# 02-CPU_BOARD.net
KiCad netlist of a schematic drawn in Altium Designer
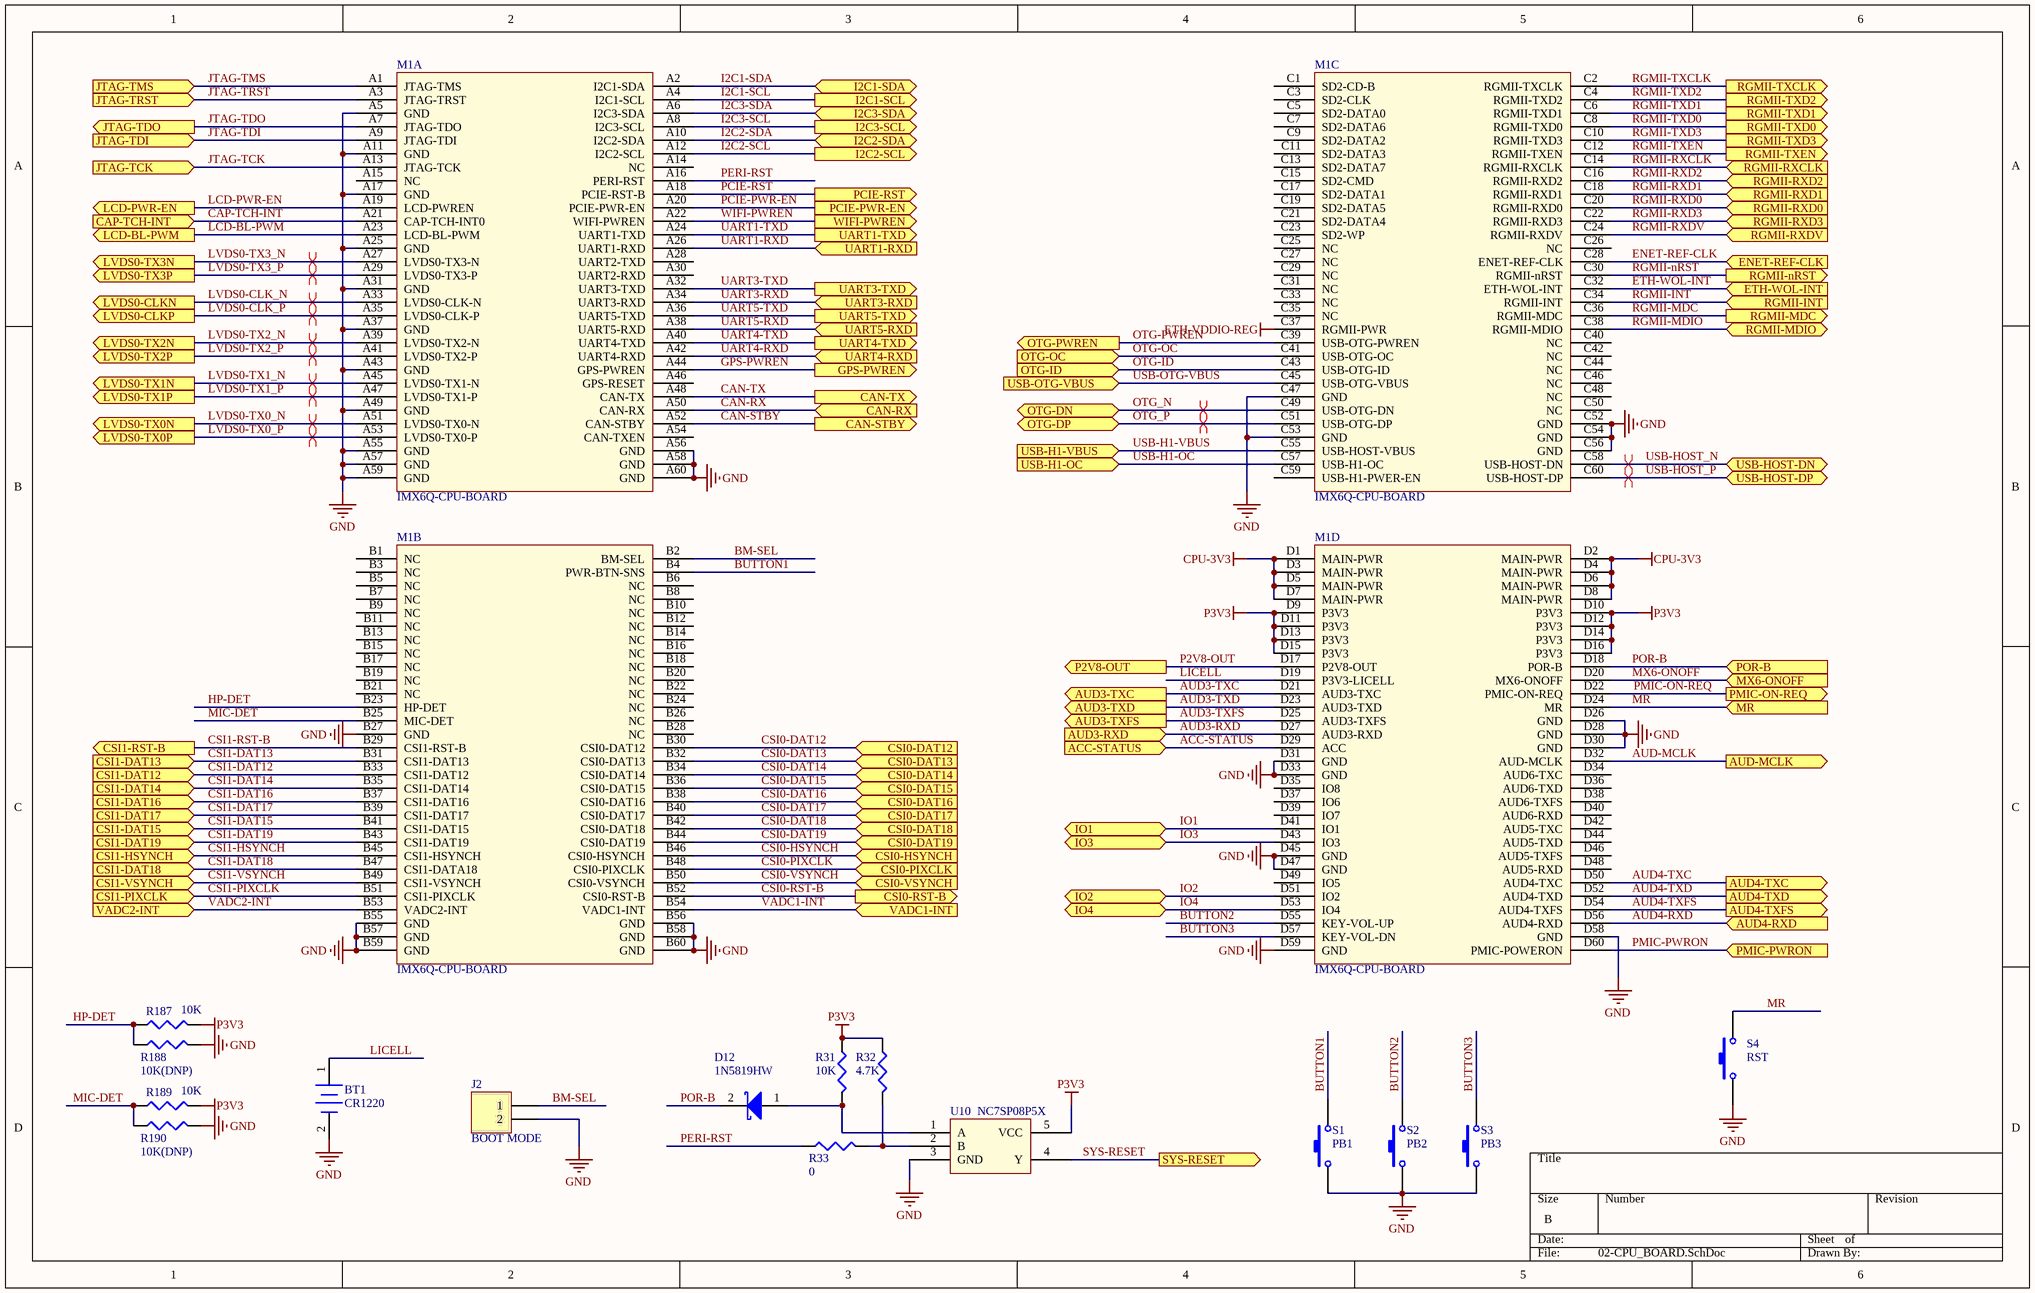
[diagram p0: 02-CPU_BOARD.SchDoc]

(export (version "E")
  (design (tool "Eeschema 10.0.6"))
  (components
    (comp (ref "BT1")
      (value "CR1220")
      (footprint "cr1220")
      (description "Multicell Battery")
      (fields (field (name "PUBLISHER") "Altium Limited"))
      (libsource (lib "Miscellaneous Devices") (part "Battery"))
    )
    (comp (ref "D12")
      (value "1N5819HW")
      (footprint "1N5819")
      (description "Schottky Rectifier")
      (libsource (lib "Miscellaneous Devices") (part "Diode 11DQ03"))
    )
    (comp (ref "J2")
      (value "BOOT MODE")
      (footprint "HDR1X2")
      (description "Header, 2-Pin")
      (fields (field (name "PUBLISHER") "Altium Limited"))
      (libsource (lib "Miscellaneous Connectors") (part "Header 2"))
    )
    (comp (ref "M1") (value "IMX6Q-CPU-BOARD") (libsource (lib "Schlib") (part "IMX6Q-CPU-BOARD")))
    (comp (ref "R31") (value "10K") (footprint "0402") (libsource (lib "*") (part "CR16-1003FM")))
    (comp (ref "R32") (value "4.7K") (footprint "0402") (libsource (lib "*") (part "CR16-1003FM")))
    (comp (ref "R33") (value "0") (footprint "0402") (libsource (lib "*") (part "CR16-1003FM")))
    (comp (ref "R187") (value "10K") (footprint "0402") (libsource (lib "*") (part "CR16-1003FM")))
    (comp (ref "R188") (value "10K(DNP)") (footprint "0402") (libsource (lib "*") (part "CR16-1003FM")))
    (comp (ref "R189") (value "10K") (footprint "0402") (libsource (lib "*") (part "CR16-1003FM")))
    (comp (ref "R190") (value "10K(DNP)") (footprint "0402") (libsource (lib "*") (part "CR16-1003FM")))
    (comp (ref "S1")
      (value "PB1")
      (footprint "SW-PB-SMD")
      (description "Switch")
      (fields (field (name "PUBLISHER") "Altium Limited"))
      (libsource (lib "Miscellaneous Devices") (part "SW-PB"))
    )
    (comp (ref "S2")
      (value "PB2")
      (footprint "SW-PB-SMD")
      (description "Switch")
      (fields (field (name "PUBLISHER") "Altium Limited"))
      (libsource (lib "Miscellaneous Devices") (part "SW-PB"))
    )
    (comp (ref "S3")
      (value "PB3")
      (footprint "SW-PB-SMD")
      (description "Switch")
      (fields (field (name "PUBLISHER") "Altium Limited"))
      (libsource (lib "Miscellaneous Devices") (part "SW-PB"))
    )
    (comp (ref "S4")
      (value "RST")
      (footprint "SW-PB-SMD")
      (description "Switch")
      (fields (field (name "PUBLISHER") "Altium Limited"))
      (libsource (lib "Miscellaneous Devices") (part "SW-PB"))
    )
    (comp (ref "U10") (value "NC7SP08P5X") (footprint "SC70") (libsource (lib "Schlib") (part "NC7SP08P5X")))
  )
  (nets
    (net (code "1") (name "/ACC-STATUS") (class "Default")
      (node (ref "M1") (pin "D29") (pinfunction "ACC_D29") (pintype "passive"))
    )
    (net (code "2") (name "/AUD-MCLK") (class "Default")
      (node (ref "M1") (pin "D32") (pinfunction "AUD-MCLK_D32") (pintype "passive"))
    )
    (net (code "3") (name "/AUD3-RXD") (class "Default")
      (node (ref "M1") (pin "D27") (pinfunction "AUD3-RXD_D27") (pintype "passive"))
    )
    (net (code "4") (name "/AUD3-TXC") (class "Default")
      (node (ref "M1") (pin "D21") (pinfunction "AUD3-TXC_D21") (pintype "passive"))
    )
    (net (code "5") (name "/AUD3-TXD") (class "Default")
      (node (ref "M1") (pin "D23") (pinfunction "AUD3-TXD_D23") (pintype "passive"))
    )
    (net (code "6") (name "/AUD3-TXFS") (class "Default")
      (node (ref "M1") (pin "D25") (pinfunction "AUD3-TXFS_D25") (pintype "passive"))
    )
    (net (code "7") (name "/AUD4-RXD") (class "Default")
      (node (ref "M1") (pin "D56") (pinfunction "AUD4-RXD_D56") (pintype "passive"))
    )
    (net (code "8") (name "/AUD4-TXC") (class "Default")
      (node (ref "M1") (pin "D50") (pinfunction "AUD4-TXC_D50") (pintype "passive"))
    )
    (net (code "9") (name "/AUD4-TXD") (class "Default")
      (node (ref "M1") (pin "D52") (pinfunction "AUD4-TXD_D52") (pintype "passive"))
    )
    (net (code "10") (name "/AUD4-TXFS") (class "Default")
      (node (ref "M1") (pin "D54") (pinfunction "AUD4-TXFS_D54") (pintype "passive"))
    )
    (net (code "11") (name "/BM-SEL") (class "Default")
      (node (ref "J2") (pin "1") (pinfunction "1_1") (pintype "passive"))
      (node (ref "M1") (pin "B2") (pinfunction "BM-SEL_B2") (pintype "passive"))
    )
    (net (code "12") (name "/BUTTON1") (class "Default")
      (node (ref "M1") (pin "B4") (pinfunction "PWR-BTN-SNS_B4") (pintype "passive"))
      (node (ref "S1") (pin "2") (pinfunction "2_2") (pintype "passive"))
    )
    (net (code "13") (name "/BUTTON2") (class "Default")
      (node (ref "M1") (pin "D55") (pinfunction "KEY-VOL-UP_D55") (pintype "passive"))
      (node (ref "S2") (pin "2") (pinfunction "2_2") (pintype "passive"))
    )
    (net (code "14") (name "/BUTTON3") (class "Default")
      (node (ref "M1") (pin "D57") (pinfunction "KEY-VOL-DN_D57") (pintype "passive"))
      (node (ref "S3") (pin "2") (pinfunction "2_2") (pintype "passive"))
    )
    (net (code "15") (name "/CAN-RX") (class "Default")
      (node (ref "M1") (pin "A50") (pinfunction "CAN-RX_A50") (pintype "passive"))
    )
    (net (code "16") (name "/CAN-STBY") (class "Default")
      (node (ref "M1") (pin "A52") (pinfunction "CAN-STBY_A52") (pintype "passive"))
    )
    (net (code "17") (name "/CAN-TX") (class "Default")
      (node (ref "M1") (pin "A48") (pinfunction "CAN-TX_A48") (pintype "passive"))
    )
    (net (code "18") (name "/CAP-TCH-INT") (class "Default")
      (node (ref "M1") (pin "A21") (pinfunction "CAP-TCH-INT0_A21") (pintype "passive"))
    )
    (net (code "19") (name "/CSI0-DAT12") (class "Default")
      (node (ref "M1") (pin "B30") (pinfunction "CSI0-DAT12_B30") (pintype "passive"))
    )
    (net (code "20") (name "/CSI0-DAT13") (class "Default")
      (node (ref "M1") (pin "B32") (pinfunction "CSI0-DAT13_B32") (pintype "passive"))
    )
    (net (code "21") (name "/CSI0-DAT14") (class "Default")
      (node (ref "M1") (pin "B34") (pinfunction "CSI0-DAT14_B34") (pintype "passive"))
    )
    (net (code "22") (name "/CSI0-DAT15") (class "Default")
      (node (ref "M1") (pin "B36") (pinfunction "CSI0-DAT15_B36") (pintype "passive"))
    )
    (net (code "23") (name "/CSI0-DAT16") (class "Default")
      (node (ref "M1") (pin "B38") (pinfunction "CSI0-DAT16_B38") (pintype "passive"))
    )
    (net (code "24") (name "/CSI0-DAT17") (class "Default")
      (node (ref "M1") (pin "B40") (pinfunction "CSI0-DAT17_B40") (pintype "passive"))
    )
    (net (code "25") (name "/CSI0-DAT18") (class "Default")
      (node (ref "M1") (pin "B42") (pinfunction "CSI0-DAT18_B42") (pintype "passive"))
    )
    (net (code "26") (name "/CSI0-DAT19") (class "Default")
      (node (ref "M1") (pin "B44") (pinfunction "CSI0-DAT19_B44") (pintype "passive"))
    )
    (net (code "27") (name "/CSI0-HSYNCH") (class "Default")
      (node (ref "M1") (pin "B46") (pinfunction "CSI0-HSYNCH_B46") (pintype "passive"))
    )
    (net (code "28") (name "/CSI0-PIXCLK") (class "Default")
      (node (ref "M1") (pin "B48") (pinfunction "CSI0-PIXCLK_B48") (pintype "passive"))
    )
    (net (code "29") (name "/CSI0-RST-B") (class "Default")
      (node (ref "M1") (pin "B52") (pinfunction "CSI0-RST-B_B52") (pintype "passive"))
    )
    (net (code "30") (name "/CSI0-VSYNCH") (class "Default")
      (node (ref "M1") (pin "B50") (pinfunction "CSI0-VSYNCH_B50") (pintype "passive"))
    )
    (net (code "31") (name "/CSI1-DAT12") (class "Default")
      (node (ref "M1") (pin "B33") (pinfunction "CSI1-DAT12_B33") (pintype "passive"))
    )
    (net (code "32") (name "/CSI1-DAT13") (class "Default")
      (node (ref "M1") (pin "B31") (pinfunction "CSI1-DAT13_B31") (pintype "passive"))
    )
    (net (code "33") (name "/CSI1-DAT14") (class "Default")
      (node (ref "M1") (pin "B35") (pinfunction "CSI1-DAT14_B35") (pintype "passive"))
    )
    (net (code "34") (name "/CSI1-DAT15") (class "Default")
      (node (ref "M1") (pin "B41") (pinfunction "CSI1-DAT15_B41") (pintype "passive"))
    )
    (net (code "35") (name "/CSI1-DAT16") (class "Default")
      (node (ref "M1") (pin "B37") (pinfunction "CSI1-DAT16_B37") (pintype "passive"))
    )
    (net (code "36") (name "/CSI1-DAT17") (class "Default")
      (node (ref "M1") (pin "B39") (pinfunction "CSI1-DAT17_B39") (pintype "passive"))
    )
    (net (code "37") (name "/CSI1-DAT18") (class "Default")
      (node (ref "M1") (pin "B47") (pinfunction "CSI1-DATA18_B47") (pintype "passive"))
    )
    (net (code "38") (name "/CSI1-DAT19") (class "Default")
      (node (ref "M1") (pin "B43") (pinfunction "CSI1-DAT19_B43") (pintype "passive"))
    )
    (net (code "39") (name "/CSI1-HSYNCH") (class "Default")
      (node (ref "M1") (pin "B45") (pinfunction "CSI1-HSYNCH_B45") (pintype "passive"))
    )
    (net (code "40") (name "/CSI1-PIXCLK") (class "Default")
      (node (ref "M1") (pin "B51") (pinfunction "CSI1-PIXCLK_B51") (pintype "passive"))
    )
    (net (code "41") (name "/CSI1-RST-B") (class "Default")
      (node (ref "M1") (pin "B29") (pinfunction "CSI1-RST-B_B29") (pintype "passive"))
    )
    (net (code "42") (name "/CSI1-VSYNCH") (class "Default")
      (node (ref "M1") (pin "B49") (pinfunction "CSI1-VSYNCH_B49") (pintype "passive"))
    )
    (net (code "43") (name "/ENET-REF-CLK") (class "Default")
      (node (ref "M1") (pin "C28") (pinfunction "ENET-REF-CLK_C28") (pintype "passive"))
    )
    (net (code "44") (name "/ETH-WOL-INT") (class "Default")
      (node (ref "M1") (pin "C32") (pinfunction "ETH-WOL-INT_C32") (pintype "passive"))
    )
    (net (code "45") (name "/GPS-PWREN") (class "Default")
      (node (ref "M1") (pin "A44") (pinfunction "GPS-PWREN_A44") (pintype "passive"))
    )
    (net (code "46") (name "/HP-DET") (class "Default")
      (node (ref "M1") (pin "B23") (pinfunction "HP-DET_B23") (pintype "passive"))
      (node (ref "R187") (pin "1") (pinfunction "1_1") (pintype "passive"))
      (node (ref "R188") (pin "1") (pinfunction "1_1") (pintype "passive"))
    )
    (net (code "47") (name "/I2C1-SCL") (class "Default")
      (node (ref "M1") (pin "A4") (pinfunction "I2C1-SCL_A4") (pintype "passive"))
    )
    (net (code "48") (name "/I2C1-SDA") (class "Default")
      (node (ref "M1") (pin "A2") (pinfunction "I2C1-SDA_A2") (pintype "passive"))
    )
    (net (code "49") (name "/I2C2-SCL") (class "Default")
      (node (ref "M1") (pin "A12") (pinfunction "I2C2-SCL_A12") (pintype "passive"))
    )
    (net (code "50") (name "/I2C2-SDA") (class "Default")
      (node (ref "M1") (pin "A10") (pinfunction "I2C2-SDA_A10") (pintype "passive"))
    )
    (net (code "51") (name "/I2C3-SCL") (class "Default")
      (node (ref "M1") (pin "A8") (pinfunction "I2C3-SCL_A8") (pintype "passive"))
    )
    (net (code "52") (name "/I2C3-SDA") (class "Default")
      (node (ref "M1") (pin "A6") (pinfunction "I2C3-SDA_A6") (pintype "passive"))
    )
    (net (code "53") (name "/IO1") (class "Default")
      (node (ref "M1") (pin "D41") (pinfunction "IO1_D41") (pintype "passive"))
    )
    (net (code "54") (name "/IO2") (class "Default")
      (node (ref "M1") (pin "D51") (pinfunction "IO2_D51") (pintype "passive"))
    )
    (net (code "55") (name "/IO3") (class "Default")
      (node (ref "M1") (pin "D43") (pinfunction "IO3_D43") (pintype "passive"))
    )
    (net (code "56") (name "/IO4") (class "Default")
      (node (ref "M1") (pin "D53") (pinfunction "IO4_D53") (pintype "passive"))
    )
    (net (code "57") (name "/JTAG-TCK") (class "Default")
      (node (ref "M1") (pin "A13") (pinfunction "JTAG-TCK_A13") (pintype "passive"))
    )
    (net (code "58") (name "/JTAG-TDI") (class "Default")
      (node (ref "M1") (pin "A9") (pinfunction "JTAG-TDI_A9") (pintype "passive"))
    )
    (net (code "59") (name "/JTAG-TDO") (class "Default")
      (node (ref "M1") (pin "A7") (pinfunction "JTAG-TDO_A7") (pintype "passive"))
    )
    (net (code "60") (name "/JTAG-TMS") (class "Default")
      (node (ref "M1") (pin "A1") (pinfunction "JTAG-TMS_A1") (pintype "passive"))
    )
    (net (code "61") (name "/JTAG-TRST") (class "Default")
      (node (ref "M1") (pin "A3") (pinfunction "JTAG-TRST_A3") (pintype "passive"))
    )
    (net (code "62") (name "/LCD-BL-PWM") (class "Default")
      (node (ref "M1") (pin "A23") (pinfunction "LCD-BL-PWM_A23") (pintype "passive"))
    )
    (net (code "63") (name "/LCD-PWR-EN") (class "Default")
      (node (ref "M1") (pin "A19") (pinfunction "LCD-PWREN_A19") (pintype "passive"))
    )
    (net (code "64") (name "/LICELL") (class "Default")
      (node (ref "BT1") (pin "1") (pinfunction "+_1") (pintype "passive"))
      (node (ref "M1") (pin "D19") (pinfunction "P3V3-LICELL_D19") (pintype "passive"))
    )
    (net (code "65") (name "/LVDS0-CLK_N") (class "Default")
      (node (ref "M1") (pin "A33") (pinfunction "LVDS0-CLK-N_A33") (pintype "passive"))
    )
    (net (code "66") (name "/LVDS0-CLK_P") (class "Default")
      (node (ref "M1") (pin "A35") (pinfunction "LVDS0-CLK-P_A35") (pintype "passive"))
    )
    (net (code "67") (name "/LVDS0-TX0_N") (class "Default")
      (node (ref "M1") (pin "A51") (pinfunction "LVDS0-TX0-N_A51") (pintype "passive"))
    )
    (net (code "68") (name "/LVDS0-TX0_P") (class "Default")
      (node (ref "M1") (pin "A53") (pinfunction "LVDS0-TX0-P_A53") (pintype "passive"))
    )
    (net (code "69") (name "/LVDS0-TX1_N") (class "Default")
      (node (ref "M1") (pin "A45") (pinfunction "LVDS0-TX1-N_A45") (pintype "passive"))
    )
    (net (code "70") (name "/LVDS0-TX1_P") (class "Default")
      (node (ref "M1") (pin "A47") (pinfunction "LVDS0-TX1-P_A47") (pintype "passive"))
    )
    (net (code "71") (name "/LVDS0-TX2_N") (class "Default")
      (node (ref "M1") (pin "A39") (pinfunction "LVDS0-TX2-N_A39") (pintype "passive"))
    )
    (net (code "72") (name "/LVDS0-TX2_P") (class "Default")
      (node (ref "M1") (pin "A41") (pinfunction "LVDS0-TX2-P_A41") (pintype "passive"))
    )
    (net (code "73") (name "/LVDS0-TX3_N") (class "Default")
      (node (ref "M1") (pin "A27") (pinfunction "LVDS0-TX3-N_A27") (pintype "passive"))
    )
    (net (code "74") (name "/LVDS0-TX3_P") (class "Default")
      (node (ref "M1") (pin "A29") (pinfunction "LVDS0-TX3-P_A29") (pintype "passive"))
    )
    (net (code "75") (name "/MIC-DET") (class "Default")
      (node (ref "M1") (pin "B25") (pinfunction "MIC-DET_B25") (pintype "passive"))
      (node (ref "R189") (pin "1") (pinfunction "1_1") (pintype "passive"))
      (node (ref "R190") (pin "1") (pinfunction "1_1") (pintype "passive"))
    )
    (net (code "76") (name "/MR") (class "Default")
      (node (ref "M1") (pin "D24") (pinfunction "MR_D24") (pintype "passive"))
      (node (ref "S4") (pin "2") (pinfunction "2_2") (pintype "passive"))
    )
    (net (code "77") (name "/MX6-ONOFF") (class "Default")
      (node (ref "M1") (pin "D20") (pinfunction "MX6-ONOFF_D20") (pintype "passive"))
    )
    (net (code "78") (name "/OTG-ID") (class "Default")
      (node (ref "M1") (pin "C43") (pinfunction "USB-OTG-ID_C43") (pintype "passive"))
    )
    (net (code "79") (name "/OTG-OC") (class "Default")
      (node (ref "M1") (pin "C41") (pinfunction "USB-OTG-OC_C41") (pintype "passive"))
    )
    (net (code "80") (name "/OTG-PWREN") (class "Default")
      (node (ref "M1") (pin "C39") (pinfunction "USB-OTG-PWREN_C39") (pintype "passive"))
    )
    (net (code "81") (name "/OTG_N") (class "Default")
      (node (ref "M1") (pin "C49") (pinfunction "USB-OTG-DN_C49") (pintype "passive"))
    )
    (net (code "82") (name "/OTG_P") (class "Default")
      (node (ref "M1") (pin "C51") (pinfunction "USB-OTG-DP_C51") (pintype "passive"))
    )
    (net (code "83") (name "/P2V8-OUT") (class "Default")
      (node (ref "M1") (pin "D17") (pinfunction "P2V8-OUT_D17") (pintype "passive"))
    )
    (net (code "84") (name "/PCIE-PWR-EN") (class "Default")
      (node (ref "M1") (pin "A20") (pinfunction "PCIE-PWR-EN_A20") (pintype "passive"))
    )
    (net (code "85") (name "/PCIE-RST") (class "Default")
      (node (ref "M1") (pin "A18") (pinfunction "PCIE-RST-B_A18") (pintype "passive"))
    )
    (net (code "86") (name "/PERI-RST") (class "Default")
      (node (ref "M1") (pin "A16") (pinfunction "PERI-RST_A16") (pintype "passive"))
      (node (ref "R33") (pin "1") (pinfunction "1_1") (pintype "passive"))
    )
    (net (code "87") (name "/PMIC-ON-REQ") (class "Default")
      (node (ref "M1") (pin "D22") (pinfunction "PMIC-ON-REQ_D22") (pintype "passive"))
    )
    (net (code "88") (name "/PMIC-PWRON") (class "Default")
      (node (ref "M1") (pin "D60") (pinfunction "PMIC-POWERON_D60") (pintype "passive"))
    )
    (net (code "89") (name "/POR-B") (class "Default")
      (node (ref "D12") (pin "2") (pinfunction "K_2") (pintype "passive"))
      (node (ref "M1") (pin "D18") (pinfunction "POR-B_D18") (pintype "passive"))
    )
    (net (code "90") (name "/RGMII-INT") (class "Default")
      (node (ref "M1") (pin "C34") (pinfunction "RGMII-INT_C34") (pintype "passive"))
    )
    (net (code "91") (name "/RGMII-MDC") (class "Default")
      (node (ref "M1") (pin "C36") (pinfunction "RGMII-MDC_C36") (pintype "passive"))
    )
    (net (code "92") (name "/RGMII-MDIO") (class "Default")
      (node (ref "M1") (pin "C38") (pinfunction "RGMII-MDIO_C38") (pintype "passive"))
    )
    (net (code "93") (name "/RGMII-RXCLK") (class "Default")
      (node (ref "M1") (pin "C14") (pinfunction "RGMII-RXCLK_C14") (pintype "passive"))
    )
    (net (code "94") (name "/RGMII-RXD0") (class "Default")
      (node (ref "M1") (pin "C20") (pinfunction "RGMII-RXD0_C20") (pintype "passive"))
    )
    (net (code "95") (name "/RGMII-RXD1") (class "Default")
      (node (ref "M1") (pin "C18") (pinfunction "RGMII-RXD1_C18") (pintype "passive"))
    )
    (net (code "96") (name "/RGMII-RXD2") (class "Default")
      (node (ref "M1") (pin "C16") (pinfunction "RGMII-RXD2_C16") (pintype "passive"))
    )
    (net (code "97") (name "/RGMII-RXD3") (class "Default")
      (node (ref "M1") (pin "C22") (pinfunction "RGMII-RXD3_C22") (pintype "passive"))
    )
    (net (code "98") (name "/RGMII-RXDV") (class "Default")
      (node (ref "M1") (pin "C24") (pinfunction "RGMII-RXDV_C24") (pintype "passive"))
    )
    (net (code "99") (name "/RGMII-TXCLK") (class "Default")
      (node (ref "M1") (pin "C2") (pinfunction "RGMII-TXCLK_C2") (pintype "passive"))
    )
    (net (code "100") (name "/RGMII-TXD0") (class "Default")
      (node (ref "M1") (pin "C8") (pinfunction "RGMII-TXD0_C8") (pintype "passive"))
    )
    (net (code "101") (name "/RGMII-TXD1") (class "Default")
      (node (ref "M1") (pin "C6") (pinfunction "RGMII-TXD1_C6") (pintype "passive"))
    )
    (net (code "102") (name "/RGMII-TXD2") (class "Default")
      (node (ref "M1") (pin "C4") (pinfunction "RGMII-TXD2_C4") (pintype "passive"))
    )
    (net (code "103") (name "/RGMII-TXD3") (class "Default")
      (node (ref "M1") (pin "C10") (pinfunction "RGMII-TXD3_C10") (pintype "passive"))
    )
    (net (code "104") (name "/RGMII-TXEN") (class "Default")
      (node (ref "M1") (pin "C12") (pinfunction "RGMII-TXEN_C12") (pintype "passive"))
    )
    (net (code "105") (name "/RGMII-nRST") (class "Default")
      (node (ref "M1") (pin "C30") (pinfunction "RGMII-nRST_C30") (pintype "passive"))
    )
    (net (code "106") (name "/SYS-RESET") (class "Default")
      (node (ref "U10") (pin "4") (pinfunction "Y_4") (pintype "passive"))
    )
    (net (code "107") (name "/UART1-RXD") (class "Default")
      (node (ref "M1") (pin "A26") (pinfunction "UART1-RXD_A26") (pintype "passive"))
    )
    (net (code "108") (name "/UART1-TXD") (class "Default")
      (node (ref "M1") (pin "A24") (pinfunction "UART1-TXD_A24") (pintype "passive"))
    )
    (net (code "109") (name "/UART3-RXD") (class "Default")
      (node (ref "M1") (pin "A34") (pinfunction "UART3-RXD_A34") (pintype "passive"))
    )
    (net (code "110") (name "/UART3-TXD") (class "Default")
      (node (ref "M1") (pin "A32") (pinfunction "UART3-TXD_A32") (pintype "passive"))
    )
    (net (code "111") (name "/UART4-RXD") (class "Default")
      (node (ref "M1") (pin "A42") (pinfunction "UART4-RXD_A42") (pintype "passive"))
    )
    (net (code "112") (name "/UART4-TXD") (class "Default")
      (node (ref "M1") (pin "A40") (pinfunction "UART4-TXD_A40") (pintype "passive"))
    )
    (net (code "113") (name "/UART5-RXD") (class "Default")
      (node (ref "M1") (pin "A38") (pinfunction "UART5-RXD_A38") (pintype "passive"))
    )
    (net (code "114") (name "/UART5-TXD") (class "Default")
      (node (ref "M1") (pin "A36") (pinfunction "UART5-TXD_A36") (pintype "passive"))
    )
    (net (code "115") (name "/USB-H1-OC") (class "Default")
      (node (ref "M1") (pin "C57") (pinfunction "USB-H1-OC_C57") (pintype "passive"))
    )
    (net (code "116") (name "/USB-H1-VBUS") (class "Default")
      (node (ref "M1") (pin "C55") (pinfunction "USB-HOST-VBUS_C55") (pintype "passive"))
    )
    (net (code "117") (name "/USB-HOST_N") (class "Default")
      (node (ref "M1") (pin "C58") (pinfunction "USB-HOST-DN_C58") (pintype "passive"))
    )
    (net (code "118") (name "/USB-HOST_P") (class "Default")
      (node (ref "M1") (pin "C60") (pinfunction "USB-HOST-DP_C60") (pintype "passive"))
    )
    (net (code "119") (name "/USB-OTG-VBUS") (class "Default")
      (node (ref "M1") (pin "C45") (pinfunction "USB-OTG-VBUS_C45") (pintype "passive"))
    )
    (net (code "120") (name "/VADC1-INT") (class "Default")
      (node (ref "M1") (pin "B54") (pinfunction "VADC1-INT_B54") (pintype "passive"))
    )
    (net (code "121") (name "/VADC2-INT") (class "Default")
      (node (ref "M1") (pin "B53") (pinfunction "VADC2-INT_B53") (pintype "passive"))
    )
    (net (code "122") (name "/WIFI-PWREN") (class "Default")
      (node (ref "M1") (pin "A22") (pinfunction "WIFI-PWREN_A22") (pintype "passive"))
    )
    (net (code "123") (name "CPU-3V3") (class "Default")
      (node (ref "M1") (pin "D1") (pinfunction "MAIN-PWR_D1") (pintype "passive"))
      (node (ref "M1") (pin "D2") (pinfunction "MAIN-PWR_D2") (pintype "passive"))
      (node (ref "M1") (pin "D3") (pinfunction "MAIN-PWR_D3") (pintype "passive"))
      (node (ref "M1") (pin "D4") (pinfunction "MAIN-PWR_D4") (pintype "passive"))
      (node (ref "M1") (pin "D5") (pinfunction "MAIN-PWR_D5") (pintype "passive"))
      (node (ref "M1") (pin "D6") (pinfunction "MAIN-PWR_D6") (pintype "passive"))
      (node (ref "M1") (pin "D7") (pinfunction "MAIN-PWR_D7") (pintype "passive"))
      (node (ref "M1") (pin "D8") (pinfunction "MAIN-PWR_D8") (pintype "passive"))
    )
    (net (code "124") (name "ETH-VDDIO-REG") (class "Default")
      (node (ref "M1") (pin "C37") (pinfunction "RGMII-PWR_C37") (pintype "passive"))
    )
    (net (code "125") (name "GND") (class "Default")
      (node (ref "BT1") (pin "2") (pinfunction "-_2") (pintype "passive"))
      (node (ref "J2") (pin "2") (pinfunction "2_2") (pintype "passive"))
      (node (ref "M1") (pin "A11") (pinfunction "GND_A11") (pintype "passive"))
      (node (ref "M1") (pin "A17") (pinfunction "GND_A17") (pintype "passive"))
      (node (ref "M1") (pin "A25") (pinfunction "GND_A25") (pintype "passive"))
      (node (ref "M1") (pin "A31") (pinfunction "GND_A31") (pintype "passive"))
      (node (ref "M1") (pin "A37") (pinfunction "GND_A37") (pintype "passive"))
      (node (ref "M1") (pin "A43") (pinfunction "GND_A43") (pintype "passive"))
      (node (ref "M1") (pin "A49") (pinfunction "GND_A49") (pintype "passive"))
      (node (ref "M1") (pin "A5") (pinfunction "GND_A5") (pintype "passive"))
      (node (ref "M1") (pin "A55") (pinfunction "GND_A55") (pintype "passive"))
      (node (ref "M1") (pin "A56") (pinfunction "GND_A56") (pintype "passive"))
      (node (ref "M1") (pin "A57") (pinfunction "GND_A57") (pintype "passive"))
      (node (ref "M1") (pin "A58") (pinfunction "GND_A58") (pintype "passive"))
      (node (ref "M1") (pin "A59") (pinfunction "GND_A59") (pintype "passive"))
      (node (ref "M1") (pin "A60") (pinfunction "GND_A60") (pintype "passive"))
      (node (ref "M1") (pin "B27") (pinfunction "GND_B27") (pintype "passive"))
      (node (ref "M1") (pin "B55") (pinfunction "GND_B55") (pintype "passive"))
      (node (ref "M1") (pin "B56") (pinfunction "GND_B56") (pintype "passive"))
      (node (ref "M1") (pin "B57") (pinfunction "GND_B57") (pintype "passive"))
      (node (ref "M1") (pin "B58") (pinfunction "GND_B58") (pintype "passive"))
      (node (ref "M1") (pin "B59") (pinfunction "GND_B59") (pintype "passive"))
      (node (ref "M1") (pin "B60") (pinfunction "GND_B60") (pintype "passive"))
      (node (ref "M1") (pin "C47") (pinfunction "GND_C47") (pintype "passive"))
      (node (ref "M1") (pin "C52") (pinfunction "GND_C52") (pintype "passive"))
      (node (ref "M1") (pin "C53") (pinfunction "GND_C53") (pintype "passive"))
      (node (ref "M1") (pin "C54") (pinfunction "GND_C54") (pintype "passive"))
      (node (ref "M1") (pin "C56") (pinfunction "GND_C56") (pintype "passive"))
      (node (ref "M1") (pin "D26") (pinfunction "GND_D26") (pintype "passive"))
      (node (ref "M1") (pin "D28") (pinfunction "GND_D28") (pintype "passive"))
      (node (ref "M1") (pin "D30") (pinfunction "GND_D30") (pintype "passive"))
      (node (ref "M1") (pin "D31") (pinfunction "GND_D31") (pintype "passive"))
      (node (ref "M1") (pin "D33") (pinfunction "GND_D33") (pintype "passive"))
      (node (ref "M1") (pin "D45") (pinfunction "GND_D45") (pintype "passive"))
      (node (ref "M1") (pin "D47") (pinfunction "GND_D47") (pintype "passive"))
      (node (ref "M1") (pin "D58") (pinfunction "GND_D58") (pintype "passive"))
      (node (ref "M1") (pin "D59") (pinfunction "GND_D59") (pintype "passive"))
      (node (ref "R188") (pin "2") (pinfunction "2_2") (pintype "passive"))
      (node (ref "R190") (pin "2") (pinfunction "2_2") (pintype "passive"))
      (node (ref "S1") (pin "1") (pinfunction "1_1") (pintype "passive"))
      (node (ref "S2") (pin "1") (pinfunction "1_1") (pintype "passive"))
      (node (ref "S3") (pin "1") (pinfunction "1_1") (pintype "passive"))
      (node (ref "S4") (pin "1") (pinfunction "1_1") (pintype "passive"))
      (node (ref "U10") (pin "3") (pinfunction "GND_3") (pintype "passive"))
    )
    (net (code "126") (name "Net-(D12-A)") (class "Default")
      (node (ref "D12") (pin "1") (pinfunction "A_1") (pintype "passive"))
      (node (ref "R31") (pin "2") (pinfunction "2_2") (pintype "passive"))
      (node (ref "U10") (pin "1") (pinfunction "A_1") (pintype "passive"))
    )
    (net (code "127") (name "Net-(U10-B)") (class "Default")
      (node (ref "R32") (pin "2") (pinfunction "2_2") (pintype "passive"))
      (node (ref "R33") (pin "2") (pinfunction "2_2") (pintype "passive"))
      (node (ref "U10") (pin "2") (pinfunction "B_2") (pintype "passive"))
    )
    (net (code "128") (name "P3V3") (class "Default")
      (node (ref "M1") (pin "D10") (pinfunction "P3V3_D10") (pintype "passive"))
      (node (ref "M1") (pin "D11") (pinfunction "P3V3_D11") (pintype "passive"))
      (node (ref "M1") (pin "D12") (pinfunction "P3V3_D12") (pintype "passive"))
      (node (ref "M1") (pin "D13") (pinfunction "P3V3_D13") (pintype "passive"))
      (node (ref "M1") (pin "D14") (pinfunction "P3V3_D14") (pintype "passive"))
      (node (ref "M1") (pin "D15") (pinfunction "P3V3_D15") (pintype "passive"))
      (node (ref "M1") (pin "D16") (pinfunction "P3V3_D16") (pintype "passive"))
      (node (ref "M1") (pin "D9") (pinfunction "P3V3_D9") (pintype "passive"))
      (node (ref "R187") (pin "2") (pinfunction "2_2") (pintype "passive"))
      (node (ref "R189") (pin "2") (pinfunction "2_2") (pintype "passive"))
      (node (ref "R31") (pin "1") (pinfunction "1_1") (pintype "passive"))
      (node (ref "R32") (pin "1") (pinfunction "1_1") (pintype "passive"))
      (node (ref "U10") (pin "5") (pinfunction "VCC_5") (pintype "passive"))
    )
    (net (code "129") (name "unconnected-(M1A-CAN-TXEN-PadA54)") (class "Default")
      (node (ref "M1") (pin "A54") (pinfunction "CAN-TXEN_A54") (pintype "passive"))
    )
    (net (code "130") (name "unconnected-(M1A-GPS-RESET-PadA46)") (class "Default")
      (node (ref "M1") (pin "A46") (pinfunction "GPS-RESET_A46") (pintype "passive"))
    )
    (net (code "131") (name "unconnected-(M1A-NC-PadA14)") (class "Default")
      (node (ref "M1") (pin "A14") (pinfunction "NC_A14") (pintype "passive"))
    )
    (net (code "132") (name "unconnected-(M1A-NC-PadA15)") (class "Default")
      (node (ref "M1") (pin "A15") (pinfunction "NC_A15") (pintype "passive"))
    )
    (net (code "133") (name "unconnected-(M1A-UART2-RXD-PadA30)") (class "Default")
      (node (ref "M1") (pin "A30") (pinfunction "UART2-RXD_A30") (pintype "passive"))
    )
    (net (code "134") (name "unconnected-(M1A-UART2-TXD-PadA28)") (class "Default")
      (node (ref "M1") (pin "A28") (pinfunction "UART2-TXD_A28") (pintype "passive"))
    )
    (net (code "135") (name "unconnected-(M1B-NC-PadB1)") (class "Default")
      (node (ref "M1") (pin "B1") (pinfunction "NC_B1") (pintype "passive"))
    )
    (net (code "136") (name "unconnected-(M1B-NC-PadB3)") (class "Default")
      (node (ref "M1") (pin "B3") (pinfunction "NC_B3") (pintype "passive"))
    )
    (net (code "137") (name "unconnected-(M1B-NC-PadB5)") (class "Default")
      (node (ref "M1") (pin "B5") (pinfunction "NC_B5") (pintype "passive"))
    )
    (net (code "138") (name "unconnected-(M1B-NC-PadB6)") (class "Default")
      (node (ref "M1") (pin "B6") (pinfunction "NC_B6") (pintype "passive"))
    )
    (net (code "139") (name "unconnected-(M1B-NC-PadB7)") (class "Default")
      (node (ref "M1") (pin "B7") (pinfunction "NC_B7") (pintype "passive"))
    )
    (net (code "140") (name "unconnected-(M1B-NC-PadB8)") (class "Default")
      (node (ref "M1") (pin "B8") (pinfunction "NC_B8") (pintype "passive"))
    )
    (net (code "141") (name "unconnected-(M1B-NC-PadB9)") (class "Default")
      (node (ref "M1") (pin "B9") (pinfunction "NC_B9") (pintype "passive"))
    )
    (net (code "142") (name "unconnected-(M1B-NC-PadB10)") (class "Default")
      (node (ref "M1") (pin "B10") (pinfunction "NC_B10") (pintype "passive"))
    )
    (net (code "143") (name "unconnected-(M1B-NC-PadB11)") (class "Default")
      (node (ref "M1") (pin "B11") (pinfunction "NC_B11") (pintype "passive"))
    )
    (net (code "144") (name "unconnected-(M1B-NC-PadB12)") (class "Default")
      (node (ref "M1") (pin "B12") (pinfunction "NC_B12") (pintype "passive"))
    )
    (net (code "145") (name "unconnected-(M1B-NC-PadB13)") (class "Default")
      (node (ref "M1") (pin "B13") (pinfunction "NC_B13") (pintype "passive"))
    )
    (net (code "146") (name "unconnected-(M1B-NC-PadB14)") (class "Default")
      (node (ref "M1") (pin "B14") (pinfunction "NC_B14") (pintype "passive"))
    )
    (net (code "147") (name "unconnected-(M1B-NC-PadB15)") (class "Default")
      (node (ref "M1") (pin "B15") (pinfunction "NC_B15") (pintype "passive"))
    )
    (net (code "148") (name "unconnected-(M1B-NC-PadB16)") (class "Default")
      (node (ref "M1") (pin "B16") (pinfunction "NC_B16") (pintype "passive"))
    )
    (net (code "149") (name "unconnected-(M1B-NC-PadB17)") (class "Default")
      (node (ref "M1") (pin "B17") (pinfunction "NC_B17") (pintype "passive"))
    )
    (net (code "150") (name "unconnected-(M1B-NC-PadB18)") (class "Default")
      (node (ref "M1") (pin "B18") (pinfunction "NC_B18") (pintype "passive"))
    )
    (net (code "151") (name "unconnected-(M1B-NC-PadB19)") (class "Default")
      (node (ref "M1") (pin "B19") (pinfunction "NC_B19") (pintype "passive"))
    )
    (net (code "152") (name "unconnected-(M1B-NC-PadB20)") (class "Default")
      (node (ref "M1") (pin "B20") (pinfunction "NC_B20") (pintype "passive"))
    )
    (net (code "153") (name "unconnected-(M1B-NC-PadB21)") (class "Default")
      (node (ref "M1") (pin "B21") (pinfunction "NC_B21") (pintype "passive"))
    )
    (net (code "154") (name "unconnected-(M1B-NC-PadB22)") (class "Default")
      (node (ref "M1") (pin "B22") (pinfunction "NC_B22") (pintype "passive"))
    )
    (net (code "155") (name "unconnected-(M1B-NC-PadB24)") (class "Default")
      (node (ref "M1") (pin "B24") (pinfunction "NC_B24") (pintype "passive"))
    )
    (net (code "156") (name "unconnected-(M1B-NC-PadB26)") (class "Default")
      (node (ref "M1") (pin "B26") (pinfunction "NC_B26") (pintype "passive"))
    )
    (net (code "157") (name "unconnected-(M1B-NC-PadB28)") (class "Default")
      (node (ref "M1") (pin "B28") (pinfunction "NC_B28") (pintype "passive"))
    )
    (net (code "158") (name "unconnected-(M1C-NC-PadC25)") (class "Default")
      (node (ref "M1") (pin "C25") (pinfunction "NC_C25") (pintype "passive"))
    )
    (net (code "159") (name "unconnected-(M1C-NC-PadC26)") (class "Default")
      (node (ref "M1") (pin "C26") (pinfunction "NC_C26") (pintype "passive"))
    )
    (net (code "160") (name "unconnected-(M1C-NC-PadC27)") (class "Default")
      (node (ref "M1") (pin "C27") (pinfunction "NC_C27") (pintype "passive"))
    )
    (net (code "161") (name "unconnected-(M1C-NC-PadC29)") (class "Default")
      (node (ref "M1") (pin "C29") (pinfunction "NC_C29") (pintype "passive"))
    )
    (net (code "162") (name "unconnected-(M1C-NC-PadC31)") (class "Default")
      (node (ref "M1") (pin "C31") (pinfunction "NC_C31") (pintype "passive"))
    )
    (net (code "163") (name "unconnected-(M1C-NC-PadC33)") (class "Default")
      (node (ref "M1") (pin "C33") (pinfunction "NC_C33") (pintype "passive"))
    )
    (net (code "164") (name "unconnected-(M1C-NC-PadC35)") (class "Default")
      (node (ref "M1") (pin "C35") (pinfunction "NC_C35") (pintype "passive"))
    )
    (net (code "165") (name "unconnected-(M1C-NC-PadC40)") (class "Default")
      (node (ref "M1") (pin "C40") (pinfunction "NC_C40") (pintype "passive"))
    )
    (net (code "166") (name "unconnected-(M1C-NC-PadC42)") (class "Default")
      (node (ref "M1") (pin "C42") (pinfunction "NC_C42") (pintype "passive"))
    )
    (net (code "167") (name "unconnected-(M1C-NC-PadC44)") (class "Default")
      (node (ref "M1") (pin "C44") (pinfunction "NC_C44") (pintype "passive"))
    )
    (net (code "168") (name "unconnected-(M1C-NC-PadC46)") (class "Default")
      (node (ref "M1") (pin "C46") (pinfunction "NC_C46") (pintype "passive"))
    )
    (net (code "169") (name "unconnected-(M1C-NC-PadC48)") (class "Default")
      (node (ref "M1") (pin "C48") (pinfunction "NC_C48") (pintype "passive"))
    )
    (net (code "170") (name "unconnected-(M1C-NC-PadC50)") (class "Default")
      (node (ref "M1") (pin "C50") (pinfunction "NC_C50") (pintype "passive"))
    )
    (net (code "171") (name "unconnected-(M1C-SD2-CD-B-PadC1)") (class "Default")
      (node (ref "M1") (pin "C1") (pinfunction "SD2-CD-B_C1") (pintype "passive"))
    )
    (net (code "172") (name "unconnected-(M1C-SD2-CLK-PadC3)") (class "Default")
      (node (ref "M1") (pin "C3") (pinfunction "SD2-CLK_C3") (pintype "passive"))
    )
    (net (code "173") (name "unconnected-(M1C-SD2-CMD-PadC15)") (class "Default")
      (node (ref "M1") (pin "C15") (pinfunction "SD2-CMD_C15") (pintype "passive"))
    )
    (net (code "174") (name "unconnected-(M1C-SD2-DATA0-PadC5)") (class "Default")
      (node (ref "M1") (pin "C5") (pinfunction "SD2-DATA0_C5") (pintype "passive"))
    )
    (net (code "175") (name "unconnected-(M1C-SD2-DATA1-PadC17)") (class "Default")
      (node (ref "M1") (pin "C17") (pinfunction "SD2-DATA1_C17") (pintype "passive"))
    )
    (net (code "176") (name "unconnected-(M1C-SD2-DATA2-PadC9)") (class "Default")
      (node (ref "M1") (pin "C9") (pinfunction "SD2-DATA2_C9") (pintype "passive"))
    )
    (net (code "177") (name "unconnected-(M1C-SD2-DATA3-PadC11)") (class "Default")
      (node (ref "M1") (pin "C11") (pinfunction "SD2-DATA3_C11") (pintype "passive"))
    )
    (net (code "178") (name "unconnected-(M1C-SD2-DATA4-PadC21)") (class "Default")
      (node (ref "M1") (pin "C21") (pinfunction "SD2-DATA4_C21") (pintype "passive"))
    )
    (net (code "179") (name "unconnected-(M1C-SD2-DATA5-PadC19)") (class "Default")
      (node (ref "M1") (pin "C19") (pinfunction "SD2-DATA5_C19") (pintype "passive"))
    )
    (net (code "180") (name "unconnected-(M1C-SD2-DATA6-PadC7)") (class "Default")
      (node (ref "M1") (pin "C7") (pinfunction "SD2-DATA6_C7") (pintype "passive"))
    )
    (net (code "181") (name "unconnected-(M1C-SD2-DATA7-PadC13)") (class "Default")
      (node (ref "M1") (pin "C13") (pinfunction "SD2-DATA7_C13") (pintype "passive"))
    )
    (net (code "182") (name "unconnected-(M1C-SD2-WP-PadC23)") (class "Default")
      (node (ref "M1") (pin "C23") (pinfunction "SD2-WP_C23") (pintype "passive"))
    )
    (net (code "183") (name "unconnected-(M1C-USB-H1-PWER-EN-PadC59)") (class "Default")
      (node (ref "M1") (pin "C59") (pinfunction "USB-H1-PWER-EN_C59") (pintype "passive"))
    )
    (net (code "184") (name "unconnected-(M1D-AUD5-RXD-PadD48)") (class "Default")
      (node (ref "M1") (pin "D48") (pinfunction "AUD5-RXD_D48") (pintype "passive"))
    )
    (net (code "185") (name "unconnected-(M1D-AUD5-TXC-PadD42)") (class "Default")
      (node (ref "M1") (pin "D42") (pinfunction "AUD5-TXC_D42") (pintype "passive"))
    )
    (net (code "186") (name "unconnected-(M1D-AUD5-TXD-PadD44)") (class "Default")
      (node (ref "M1") (pin "D44") (pinfunction "AUD5-TXD_D44") (pintype "passive"))
    )
    (net (code "187") (name "unconnected-(M1D-AUD5-TXFS-PadD46)") (class "Default")
      (node (ref "M1") (pin "D46") (pinfunction "AUD5-TXFS_D46") (pintype "passive"))
    )
    (net (code "188") (name "unconnected-(M1D-AUD6-RXD-PadD40)") (class "Default")
      (node (ref "M1") (pin "D40") (pinfunction "AUD6-RXD_D40") (pintype "passive"))
    )
    (net (code "189") (name "unconnected-(M1D-AUD6-TXC-PadD34)") (class "Default")
      (node (ref "M1") (pin "D34") (pinfunction "AUD6-TXC_D34") (pintype "passive"))
    )
    (net (code "190") (name "unconnected-(M1D-AUD6-TXD-PadD36)") (class "Default")
      (node (ref "M1") (pin "D36") (pinfunction "AUD6-TXD_D36") (pintype "passive"))
    )
    (net (code "191") (name "unconnected-(M1D-AUD6-TXFS-PadD38)") (class "Default")
      (node (ref "M1") (pin "D38") (pinfunction "AUD6-TXFS_D38") (pintype "passive"))
    )
    (net (code "192") (name "unconnected-(M1D-IO5-PadD49)") (class "Default")
      (node (ref "M1") (pin "D49") (pinfunction "IO5_D49") (pintype "passive"))
    )
    (net (code "193") (name "unconnected-(M1D-IO6-PadD37)") (class "Default")
      (node (ref "M1") (pin "D37") (pinfunction "IO6_D37") (pintype "passive"))
    )
    (net (code "194") (name "unconnected-(M1D-IO7-PadD39)") (class "Default")
      (node (ref "M1") (pin "D39") (pinfunction "IO7_D39") (pintype "passive"))
    )
    (net (code "195") (name "unconnected-(M1D-IO8-PadD35)") (class "Default")
      (node (ref "M1") (pin "D35") (pinfunction "IO8_D35") (pintype "passive"))
    )
  )
)
